# S7CAS-PLEIADES-CARTE-MERE_P20_DAC-ADC-De.net
KiCad netlist of a schematic drawn in Altium Designer
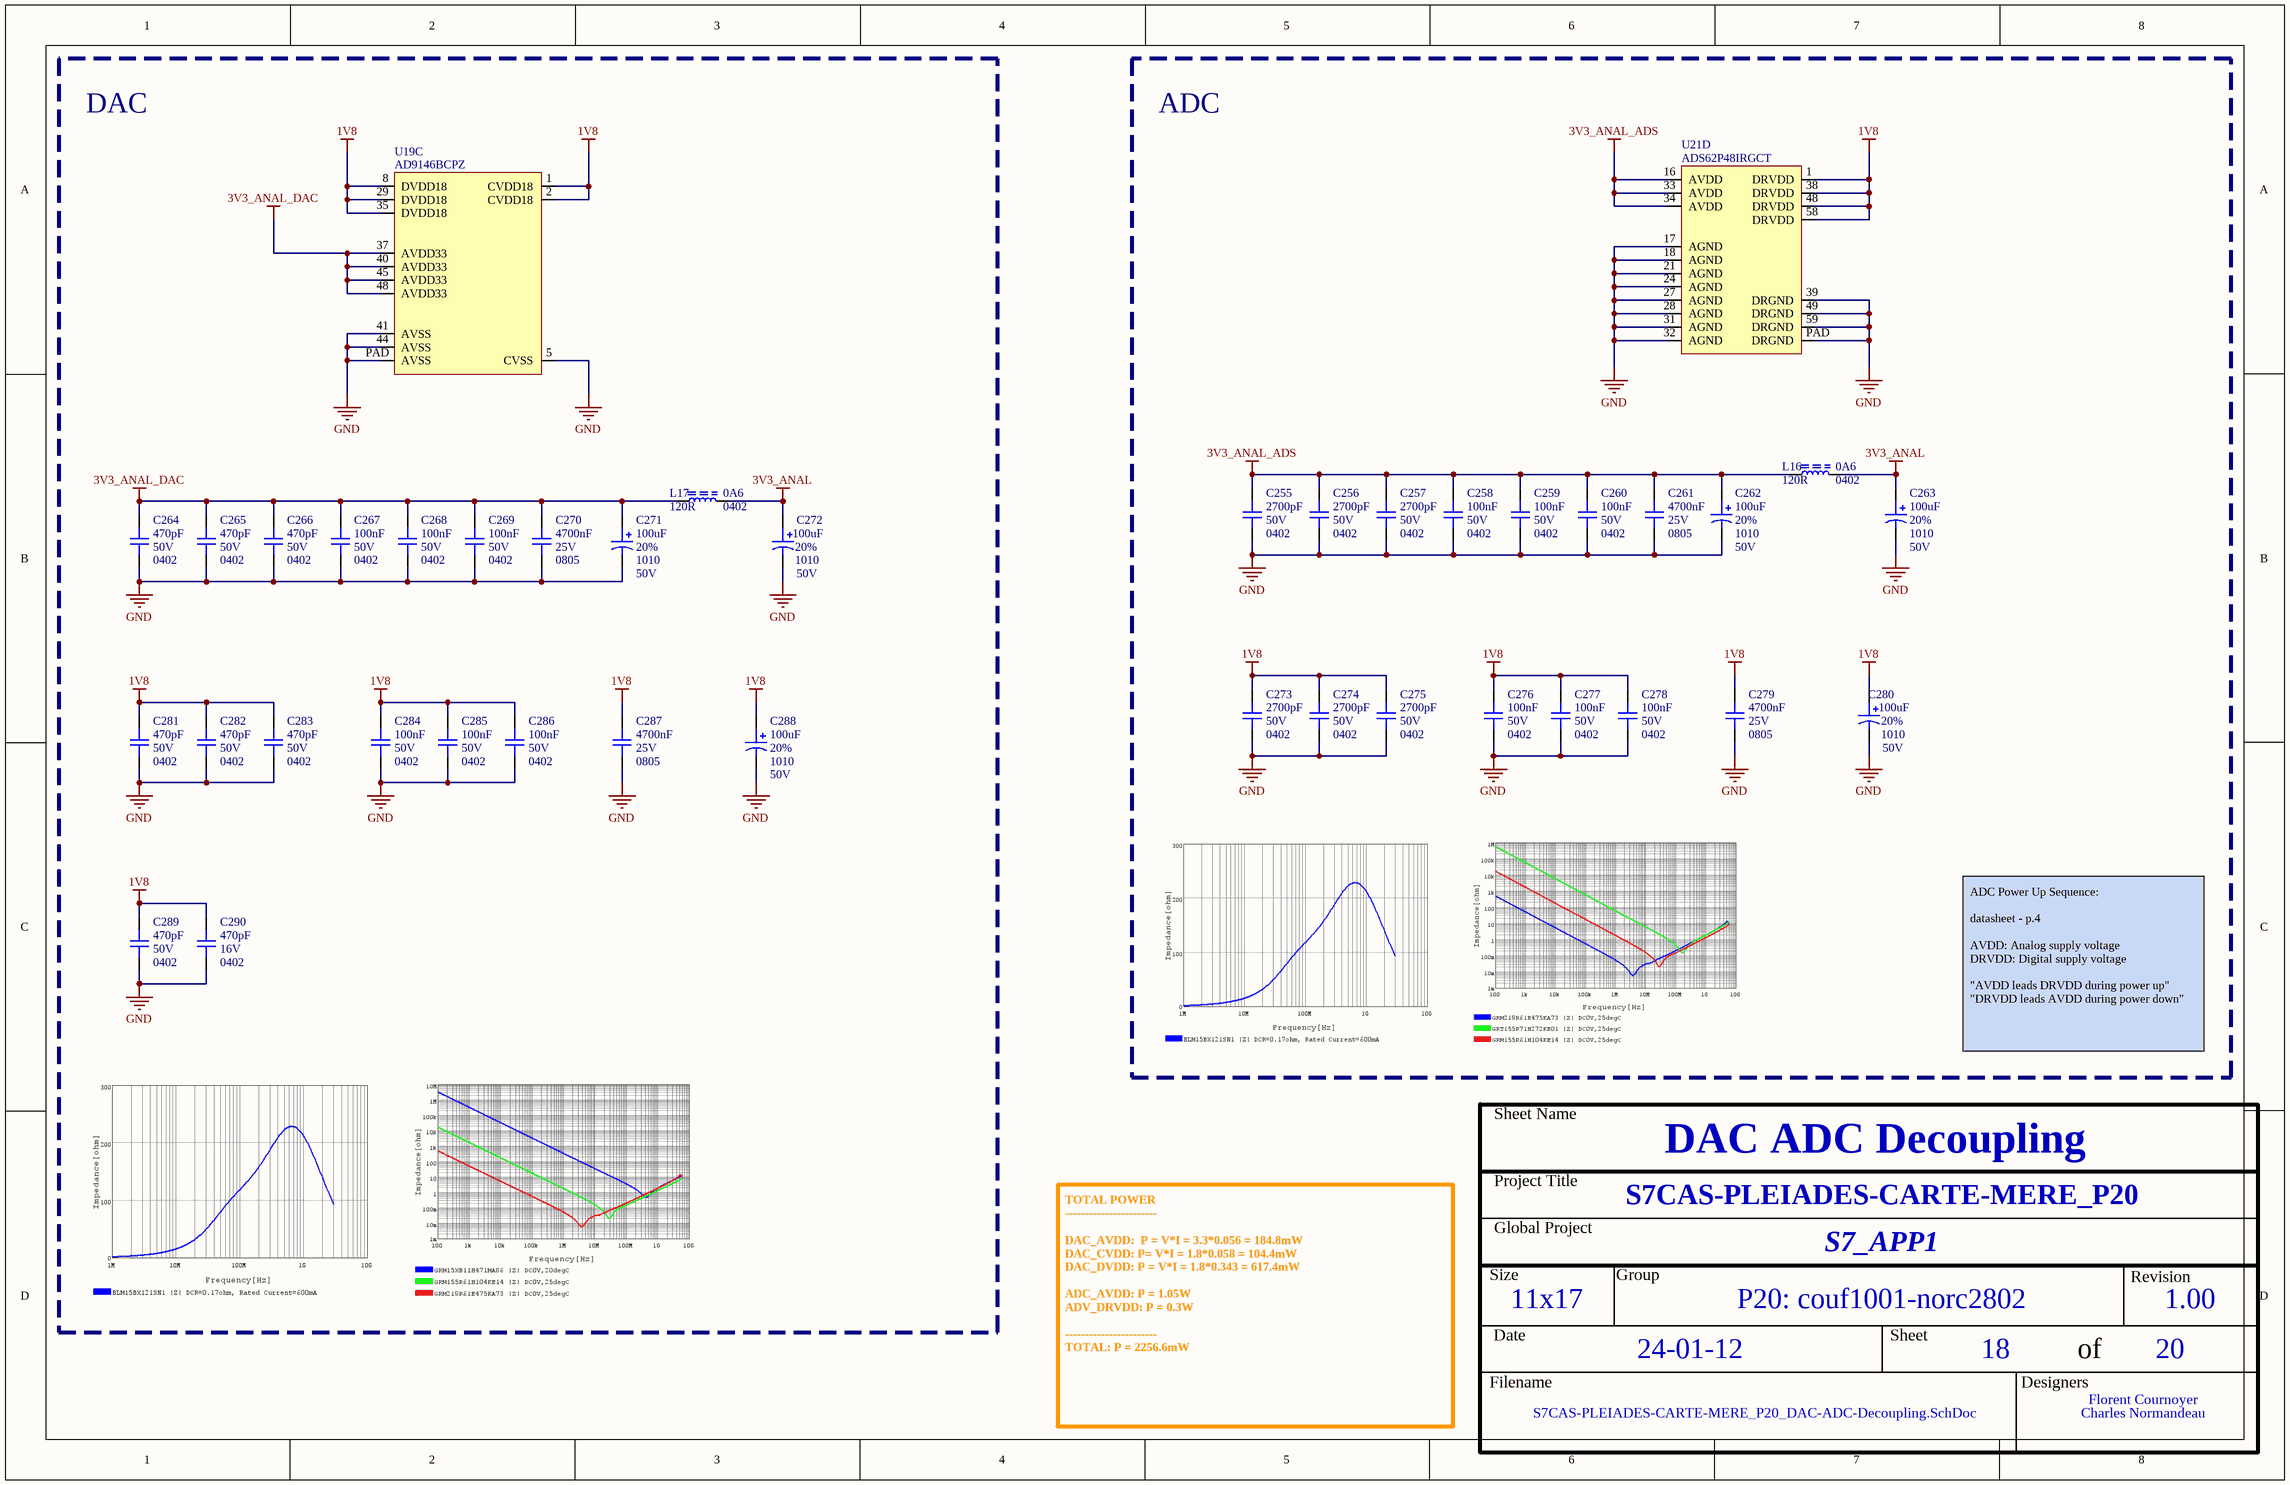
[diagram p0: S7CAS-PLEIADES-CARTE-MERE_P20_DAC-ADC-Decoupling.SchDoc]

(export (version "E")
  (design (tool "Eeschema 10.0.6"))
  (components
    (comp (ref "C255")
      (value "2700pF")
      (footprint "CAP_0402")
      (description "CAP - 0402")
      (fields
        (field (name "MFG PART NUMBER") "GRT155R71H272KE01")
        (field (name "VOLTAGE") "50V")
        (field (name "PACKAGE") "0402")
        (field (name "CREATEDBY") "Jonathan Bouchard")
      )
      (libsource (lib "S7CAS_LIB2023") (part "CAP - 0402"))
    )
    (comp (ref "C256")
      (value "2700pF")
      (footprint "CAP_0402")
      (description "CAP - 0402")
      (fields
        (field (name "MFG PART NUMBER") "GRT155R71H272KE01")
        (field (name "VOLTAGE") "50V")
        (field (name "PACKAGE") "0402")
        (field (name "CREATEDBY") "Jonathan Bouchard")
      )
      (libsource (lib "S7CAS_LIB2023") (part "CAP - 0402"))
    )
    (comp (ref "C257")
      (value "2700pF")
      (footprint "CAP_0402")
      (description "CAP - 0402")
      (fields
        (field (name "MFG PART NUMBER") "GRT155R71H272KE01")
        (field (name "VOLTAGE") "50V")
        (field (name "PACKAGE") "0402")
        (field (name "CREATEDBY") "Jonathan Bouchard")
      )
      (libsource (lib "S7CAS_LIB2023") (part "CAP - 0402"))
    )
    (comp (ref "C258")
      (value "100nF")
      (footprint "CAP_0402")
      (description "CAP - 0402")
      (fields
        (field (name "MFG PART NUMBER") "GRM155R61H104KE14")
        (field (name "VOLTAGE") "50V")
        (field (name "PACKAGE") "0402")
        (field (name "CREATEDBY") "Jonathan Bouchard")
      )
      (libsource (lib "S7CAS_LIB2023") (part "CAP - 0402"))
    )
    (comp (ref "C259")
      (value "100nF")
      (footprint "CAP_0402")
      (description "CAP - 0402")
      (fields
        (field (name "MFG PART NUMBER") "GRM155R61H104KE14")
        (field (name "VOLTAGE") "50V")
        (field (name "PACKAGE") "0402")
        (field (name "CREATEDBY") "Jonathan Bouchard")
      )
      (libsource (lib "S7CAS_LIB2023") (part "CAP - 0402"))
    )
    (comp (ref "C260")
      (value "100nF")
      (footprint "CAP_0402")
      (description "CAP - 0402")
      (fields
        (field (name "MFG PART NUMBER") "GRM155R61H104KE14")
        (field (name "VOLTAGE") "50V")
        (field (name "PACKAGE") "0402")
        (field (name "CREATEDBY") "Jonathan Bouchard")
      )
      (libsource (lib "S7CAS_LIB2023") (part "CAP - 0402"))
    )
    (comp (ref "C261")
      (value "4700nF")
      (footprint "CAP_0805")
      (description "CAP - 0805")
      (fields
        (field (name "MFG PART NUMBER") "GRM219R61E475KA73")
        (field (name "VOLTAGE") "25V")
        (field (name "PACKAGE") "0805")
        (field (name "CREATEDBY") "Jonathan Bouchard")
      )
      (libsource (lib "S7CAS_LIB2023") (part "CAP - 0805"))
    )
    (comp (ref "C262")
      (value "100uF")
      (footprint "CAP_ALU_1010_vishay")
      (description "CAP - ALU 100uF 20% 50V - 1010")
      (fields
        (field (name "MFG") "Vishay Dale")
        (field (name "MFG PART NUMBER") "MAL215099101E3")
        (field (name "VOLTAGE") "50V")
        (field (name "PACKAGE") "1010")
        (field (name "PRECISION") "20%")
        (field (name "CREATEDBY") "Jonathan Bouchard")
      )
      (libsource (lib "S7CAS_LIB2023") (part "CAP_ALU_MAL215099101E3"))
    )
    (comp (ref "C263")
      (value "100uF")
      (footprint "CAP_ALU_1010_vishay")
      (description "CAP - ALU 100uF 20% 50V - 1010")
      (fields
        (field (name "MFG") "Vishay Dale")
        (field (name "MFG PART NUMBER") "MAL215099101E3")
        (field (name "VOLTAGE") "50V")
        (field (name "PACKAGE") "1010")
        (field (name "PRECISION") "20%")
        (field (name "CREATEDBY") "Jonathan Bouchard")
      )
      (libsource (lib "S7CAS_LIB2023") (part "CAP_ALU_MAL215099101E3"))
    )
    (comp (ref "C264")
      (value "470pF")
      (footprint "CAP_0402")
      (description "CAP - 0402")
      (fields
        (field (name "MFG PART NUMBER") "GRM1555C1H471GA01")
        (field (name "VOLTAGE") "50V")
        (field (name "PACKAGE") "0402")
        (field (name "CREATEDBY") "Jonathan Bouchard")
      )
      (libsource (lib "S7CAS_LIB2023") (part "CAP - 0402"))
    )
    (comp (ref "C265")
      (value "470pF")
      (footprint "CAP_0402")
      (description "CAP - 0402")
      (fields
        (field (name "MFG PART NUMBER") "GRM1555C1H471GA01")
        (field (name "VOLTAGE") "50V")
        (field (name "PACKAGE") "0402")
        (field (name "CREATEDBY") "Jonathan Bouchard")
      )
      (libsource (lib "S7CAS_LIB2023") (part "CAP - 0402"))
    )
    (comp (ref "C266")
      (value "470pF")
      (footprint "CAP_0402")
      (description "CAP - 0402")
      (fields
        (field (name "MFG PART NUMBER") "GRM1555C1H471GA01")
        (field (name "VOLTAGE") "50V")
        (field (name "PACKAGE") "0402")
        (field (name "CREATEDBY") "Jonathan Bouchard")
      )
      (libsource (lib "S7CAS_LIB2023") (part "CAP - 0402"))
    )
    (comp (ref "C267")
      (value "100nF")
      (footprint "CAP_0402")
      (description "CAP - 0402")
      (fields
        (field (name "MFG PART NUMBER") "GRM155R61H104KE14")
        (field (name "VOLTAGE") "50V")
        (field (name "PACKAGE") "0402")
        (field (name "CREATEDBY") "Jonathan Bouchard")
      )
      (libsource (lib "S7CAS_LIB2023") (part "CAP - 0402"))
    )
    (comp (ref "C268")
      (value "100nF")
      (footprint "CAP_0402")
      (description "CAP - 0402")
      (fields
        (field (name "MFG PART NUMBER") "GRM155R61H104KE14")
        (field (name "VOLTAGE") "50V")
        (field (name "PACKAGE") "0402")
        (field (name "CREATEDBY") "Jonathan Bouchard")
      )
      (libsource (lib "S7CAS_LIB2023") (part "CAP - 0402"))
    )
    (comp (ref "C269")
      (value "100nF")
      (footprint "CAP_0402")
      (description "CAP - 0402")
      (fields
        (field (name "MFG PART NUMBER") "GRM155R61H104KE14")
        (field (name "VOLTAGE") "50V")
        (field (name "PACKAGE") "0402")
        (field (name "CREATEDBY") "Jonathan Bouchard")
      )
      (libsource (lib "S7CAS_LIB2023") (part "CAP - 0402"))
    )
    (comp (ref "C270")
      (value "4700nF")
      (footprint "CAP_0805")
      (description "CAP - 0805")
      (fields
        (field (name "MFG PART NUMBER") "GRM219R61E475KA73")
        (field (name "VOLTAGE") "25V")
        (field (name "PACKAGE") "0805")
        (field (name "CREATEDBY") "Jonathan Bouchard")
      )
      (libsource (lib "S7CAS_LIB2023") (part "CAP - 0805"))
    )
    (comp (ref "C271")
      (value "100uF")
      (footprint "CAP_ALU_1010_vishay")
      (description "CAP - ALU 100uF 20% 50V - 1010")
      (fields
        (field (name "MFG") "Vishay Dale")
        (field (name "MFG PART NUMBER") "MAL215099101E3")
        (field (name "VOLTAGE") "50V")
        (field (name "PACKAGE") "1010")
        (field (name "PRECISION") "20%")
        (field (name "CREATEDBY") "Jonathan Bouchard")
      )
      (libsource (lib "S7CAS_LIB2023") (part "CAP_ALU_MAL215099101E3"))
    )
    (comp (ref "C272")
      (value "100uF")
      (footprint "CAP_ALU_1010_vishay")
      (description "CAP - ALU 100uF 20% 50V - 1010")
      (fields
        (field (name "MFG") "Vishay Dale")
        (field (name "MFG PART NUMBER") "MAL215099101E3")
        (field (name "VOLTAGE") "50V")
        (field (name "PACKAGE") "1010")
        (field (name "PRECISION") "20%")
        (field (name "CREATEDBY") "Jonathan Bouchard")
      )
      (libsource (lib "S7CAS_LIB2023") (part "CAP_ALU_MAL215099101E3"))
    )
    (comp (ref "C273")
      (value "2700pF")
      (footprint "CAP_0402")
      (description "CAP - 0402")
      (fields
        (field (name "MFG PART NUMBER") "GRT155R71H272KE01")
        (field (name "VOLTAGE") "50V")
        (field (name "PACKAGE") "0402")
        (field (name "CREATEDBY") "Jonathan Bouchard")
      )
      (libsource (lib "S7CAS_LIB2023") (part "CAP - 0402"))
    )
    (comp (ref "C274")
      (value "2700pF")
      (footprint "CAP_0402")
      (description "CAP - 0402")
      (fields
        (field (name "MFG PART NUMBER") "GRT155R71H272KE01")
        (field (name "VOLTAGE") "50V")
        (field (name "PACKAGE") "0402")
        (field (name "CREATEDBY") "Jonathan Bouchard")
      )
      (libsource (lib "S7CAS_LIB2023") (part "CAP - 0402"))
    )
    (comp (ref "C275")
      (value "2700pF")
      (footprint "CAP_0402")
      (description "CAP - 0402")
      (fields
        (field (name "MFG PART NUMBER") "GRT155R71H272KE01")
        (field (name "VOLTAGE") "50V")
        (field (name "PACKAGE") "0402")
        (field (name "CREATEDBY") "Jonathan Bouchard")
      )
      (libsource (lib "S7CAS_LIB2023") (part "CAP - 0402"))
    )
    (comp (ref "C276")
      (value "100nF")
      (footprint "CAP_0402")
      (description "CAP - 0402")
      (fields
        (field (name "MFG PART NUMBER") "GRM155R61H104KE14")
        (field (name "VOLTAGE") "50V")
        (field (name "PACKAGE") "0402")
        (field (name "CREATEDBY") "Jonathan Bouchard")
      )
      (libsource (lib "S7CAS_LIB2023") (part "CAP - 0402"))
    )
    (comp (ref "C277")
      (value "100nF")
      (footprint "CAP_0402")
      (description "CAP - 0402")
      (fields
        (field (name "MFG PART NUMBER") "GRM155R61H104KE14")
        (field (name "VOLTAGE") "50V")
        (field (name "PACKAGE") "0402")
        (field (name "CREATEDBY") "Jonathan Bouchard")
      )
      (libsource (lib "S7CAS_LIB2023") (part "CAP - 0402"))
    )
    (comp (ref "C278")
      (value "100nF")
      (footprint "CAP_0402")
      (description "CAP - 0402")
      (fields
        (field (name "MFG PART NUMBER") "GRM155R61H104KE14")
        (field (name "VOLTAGE") "50V")
        (field (name "PACKAGE") "0402")
        (field (name "CREATEDBY") "Jonathan Bouchard")
      )
      (libsource (lib "S7CAS_LIB2023") (part "CAP - 0402"))
    )
    (comp (ref "C279")
      (value "4700nF")
      (footprint "CAP_0805")
      (description "CAP - 0805")
      (fields
        (field (name "MFG PART NUMBER") "GRM219R61E475KA73")
        (field (name "VOLTAGE") "25V")
        (field (name "PACKAGE") "0805")
        (field (name "CREATEDBY") "Jonathan Bouchard")
      )
      (libsource (lib "S7CAS_LIB2023") (part "CAP - 0805"))
    )
    (comp (ref "C280")
      (value "100uF")
      (footprint "CAP_ALU_1010_vishay")
      (description "CAP - ALU 100uF 20% 50V - 1010")
      (fields
        (field (name "MFG") "Vishay Dale")
        (field (name "MFG PART NUMBER") "MAL215099101E3")
        (field (name "VOLTAGE") "50V")
        (field (name "PACKAGE") "1010")
        (field (name "PRECISION") "20%")
        (field (name "CREATEDBY") "Jonathan Bouchard")
      )
      (libsource (lib "S7CAS_LIB2023") (part "CAP_ALU_MAL215099101E3"))
    )
    (comp (ref "C281")
      (value "470pF")
      (footprint "CAP_0402")
      (description "CAP - 0402")
      (fields
        (field (name "MFG PART NUMBER") "GRM1555C1H471GA01")
        (field (name "VOLTAGE") "50V")
        (field (name "PACKAGE") "0402")
        (field (name "CREATEDBY") "Jonathan Bouchard")
      )
      (libsource (lib "S7CAS_LIB2023") (part "CAP - 0402"))
    )
    (comp (ref "C282")
      (value "470pF")
      (footprint "CAP_0402")
      (description "CAP - 0402")
      (fields
        (field (name "MFG PART NUMBER") "GRM1555C1H471GA01")
        (field (name "VOLTAGE") "50V")
        (field (name "PACKAGE") "0402")
        (field (name "CREATEDBY") "Jonathan Bouchard")
      )
      (libsource (lib "S7CAS_LIB2023") (part "CAP - 0402"))
    )
    (comp (ref "C283")
      (value "470pF")
      (footprint "CAP_0402")
      (description "CAP - 0402")
      (fields
        (field (name "MFG PART NUMBER") "GRM1555C1H471GA01")
        (field (name "VOLTAGE") "50V")
        (field (name "PACKAGE") "0402")
        (field (name "CREATEDBY") "Jonathan Bouchard")
      )
      (libsource (lib "S7CAS_LIB2023") (part "CAP - 0402"))
    )
    (comp (ref "C284")
      (value "100nF")
      (footprint "CAP_0402")
      (description "CAP - 0402")
      (fields
        (field (name "MFG PART NUMBER") "GRM155R61H104KE14")
        (field (name "VOLTAGE") "50V")
        (field (name "PACKAGE") "0402")
        (field (name "CREATEDBY") "Jonathan Bouchard")
      )
      (libsource (lib "S7CAS_LIB2023") (part "CAP - 0402"))
    )
    (comp (ref "C285")
      (value "100nF")
      (footprint "CAP_0402")
      (description "CAP - 0402")
      (fields
        (field (name "MFG PART NUMBER") "GRM155R61H104KE14")
        (field (name "VOLTAGE") "50V")
        (field (name "PACKAGE") "0402")
        (field (name "CREATEDBY") "Jonathan Bouchard")
      )
      (libsource (lib "S7CAS_LIB2023") (part "CAP - 0402"))
    )
    (comp (ref "C286")
      (value "100nF")
      (footprint "CAP_0402")
      (description "CAP - 0402")
      (fields
        (field (name "MFG PART NUMBER") "GRM155R61H104KE14")
        (field (name "VOLTAGE") "50V")
        (field (name "PACKAGE") "0402")
        (field (name "CREATEDBY") "Jonathan Bouchard")
      )
      (libsource (lib "S7CAS_LIB2023") (part "CAP - 0402"))
    )
    (comp (ref "C287")
      (value "4700nF")
      (footprint "CAP_0805")
      (description "CAP - 0805")
      (fields
        (field (name "MFG PART NUMBER") "GRM219R61E475KA73")
        (field (name "VOLTAGE") "25V")
        (field (name "PACKAGE") "0805")
        (field (name "CREATEDBY") "Jonathan Bouchard")
      )
      (libsource (lib "S7CAS_LIB2023") (part "CAP - 0805"))
    )
    (comp (ref "C288")
      (value "100uF")
      (footprint "CAP_ALU_1010_vishay")
      (description "CAP - ALU 100uF 20% 50V - 1010")
      (fields
        (field (name "MFG") "Vishay Dale")
        (field (name "MFG PART NUMBER") "MAL215099101E3")
        (field (name "VOLTAGE") "50V")
        (field (name "PACKAGE") "1010")
        (field (name "PRECISION") "20%")
        (field (name "CREATEDBY") "Jonathan Bouchard")
      )
      (libsource (lib "S7CAS_LIB2023") (part "CAP_ALU_MAL215099101E3"))
    )
    (comp (ref "C289")
      (value "470pF")
      (footprint "CAP_0402")
      (description "CAP - 0402")
      (fields
        (field (name "MFG PART NUMBER") "GRM1555C1H471GA01")
        (field (name "VOLTAGE") "50V")
        (field (name "PACKAGE") "0402")
        (field (name "CREATEDBY") "Jonathan Bouchard")
      )
      (libsource (lib "S7CAS_LIB2023") (part "CAP - 0402"))
    )
    (comp (ref "C290")
      (value "470pF")
      (footprint "CAP_0402")
      (description "CAP - 0402")
      (fields
        (field (name "MFG PART NUMBER") "GRM15XB11H471MA86")
        (field (name "VOLTAGE") "16V")
        (field (name "PACKAGE") "0402")
        (field (name "CREATEDBY") "Jonathan Bouchard")
      )
      (libsource (lib "S7CAS_LIB2023") (part "CAP - 0402"))
    )
    (comp (ref "L16")
      (value "120R")
      (footprint "FER_0402")
      (description "FER - 0402")
      (fields
        (field (name "MFG PART NUMBER") "BLM15BX121SN1")
        (field (name "CURRENT") "0A6")
        (field (name "PACKAGE") "0402")
        (field (name "CREATEDBY") "Jonathan Bouchard")
      )
      (libsource (lib "S7CAS_LIB2023") (part "FER - 0402"))
    )
    (comp (ref "L17")
      (value "120R")
      (footprint "FER_0402")
      (description "FER - 0402")
      (fields
        (field (name "MFG PART NUMBER") "BLM15BX121SN1")
        (field (name "CURRENT") "0A6")
        (field (name "PACKAGE") "0402")
        (field (name "CREATEDBY") "Jonathan Bouchard")
      )
      (libsource (lib "S7CAS_LIB2023") (part "FER - 0402"))
    )
    (comp (ref "U19")
      (value "AD9146BCPZ")
      (footprint "DAC_AD9146BCPZ")
      (description "DAC - 16BIT SRL HIGH SPEED - QFN-48")
      (fields
        (field (name "VOLTAGE") "3.13 V ~ 3.47 V / 1.71 V ~ 1.89 V")
        (field (name "MFG") "Analog Devices Inc.")
        (field (name "CREATEDBY") "Jonathan Bouchard")
      )
      (libsource (lib "S7CAS_LIB2023") (part "DAC_AD9146BCPZ"))
    )
    (comp (ref "U21")
      (value "ADS62P48IRGCT")
      (footprint "ADC_ADS62P48IRGCT")
      (description "ADC - 14 BIT 210MSPS SUAL - VQFN-64")
      (fields
        (field (name "VOLTAGE") "3.15 V ~ 3.6 V / 1.7 V ~ 1.9 V")
        (field (name "MFG") "Texas Instruments")
        (field (name "CREATEDBY") "Jonathan Bouchard")
      )
      (libsource (lib "S7CAS_LIB2023") (part "ADC_ADS62P48IRGCT"))
    )
  )
  (nets
    (net (code "1") (name "1V8") (class "Default")
      (node (ref "C273") (pin "2") (pinfunction "2_2") (pintype "passive"))
      (node (ref "C274") (pin "2") (pinfunction "2_2") (pintype "passive"))
      (node (ref "C275") (pin "2") (pinfunction "2_2") (pintype "passive"))
      (node (ref "C276") (pin "2") (pinfunction "2_2") (pintype "passive"))
      (node (ref "C277") (pin "2") (pinfunction "2_2") (pintype "passive"))
      (node (ref "C278") (pin "2") (pinfunction "2_2") (pintype "passive"))
      (node (ref "C279") (pin "2") (pinfunction "2_2") (pintype "passive"))
      (node (ref "C280") (pin "1") (pinfunction "1_1") (pintype "passive"))
      (node (ref "C281") (pin "2") (pinfunction "2_2") (pintype "passive"))
      (node (ref "C282") (pin "2") (pinfunction "2_2") (pintype "passive"))
      (node (ref "C283") (pin "2") (pinfunction "2_2") (pintype "passive"))
      (node (ref "C284") (pin "2") (pinfunction "2_2") (pintype "passive"))
      (node (ref "C285") (pin "2") (pinfunction "2_2") (pintype "passive"))
      (node (ref "C286") (pin "2") (pinfunction "2_2") (pintype "passive"))
      (node (ref "C287") (pin "2") (pinfunction "2_2") (pintype "passive"))
      (node (ref "C288") (pin "1") (pinfunction "1_1") (pintype "passive"))
      (node (ref "C289") (pin "2") (pinfunction "2_2") (pintype "passive"))
      (node (ref "C290") (pin "2") (pinfunction "2_2") (pintype "passive"))
      (node (ref "U19") (pin "1") (pinfunction "CVDD18_1") (pintype "passive"))
      (node (ref "U19") (pin "2") (pinfunction "CVDD18_2") (pintype "passive"))
      (node (ref "U19") (pin "29") (pinfunction "DVDD18_29") (pintype "passive"))
      (node (ref "U19") (pin "35") (pinfunction "DVDD18_35") (pintype "passive"))
      (node (ref "U19") (pin "8") (pinfunction "DVDD18_8") (pintype "passive"))
      (node (ref "U21") (pin "1") (pinfunction "DRVDD_1") (pintype "passive"))
      (node (ref "U21") (pin "38") (pinfunction "DRVDD_38") (pintype "passive"))
      (node (ref "U21") (pin "48") (pinfunction "DRVDD_48") (pintype "passive"))
      (node (ref "U21") (pin "58") (pinfunction "DRVDD_58") (pintype "passive"))
    )
    (net (code "2") (name "3V3_ANAL") (class "Default")
      (node (ref "C263") (pin "1") (pinfunction "1_1") (pintype "passive"))
      (node (ref "C272") (pin "1") (pinfunction "1_1") (pintype "passive"))
      (node (ref "L16") (pin "1") (pinfunction "1_1") (pintype "passive"))
      (node (ref "L17") (pin "1") (pinfunction "1_1") (pintype "passive"))
    )
    (net (code "3") (name "3V3_ANAL_ADS") (class "Default")
      (node (ref "C255") (pin "2") (pinfunction "2_2") (pintype "passive"))
      (node (ref "C256") (pin "2") (pinfunction "2_2") (pintype "passive"))
      (node (ref "C257") (pin "2") (pinfunction "2_2") (pintype "passive"))
      (node (ref "C258") (pin "2") (pinfunction "2_2") (pintype "passive"))
      (node (ref "C259") (pin "2") (pinfunction "2_2") (pintype "passive"))
      (node (ref "C260") (pin "2") (pinfunction "2_2") (pintype "passive"))
      (node (ref "C261") (pin "2") (pinfunction "2_2") (pintype "passive"))
      (node (ref "C262") (pin "1") (pinfunction "1_1") (pintype "passive"))
      (node (ref "L16") (pin "2") (pinfunction "2_2") (pintype "passive"))
      (node (ref "U21") (pin "16") (pinfunction "AVDD_16") (pintype "passive"))
      (node (ref "U21") (pin "33") (pinfunction "AVDD_33") (pintype "passive"))
      (node (ref "U21") (pin "34") (pinfunction "AVDD_34") (pintype "passive"))
    )
    (net (code "4") (name "3V3_ANAL_DAC") (class "Default")
      (node (ref "C264") (pin "2") (pinfunction "2_2") (pintype "passive"))
      (node (ref "C265") (pin "2") (pinfunction "2_2") (pintype "passive"))
      (node (ref "C266") (pin "2") (pinfunction "2_2") (pintype "passive"))
      (node (ref "C267") (pin "2") (pinfunction "2_2") (pintype "passive"))
      (node (ref "C268") (pin "2") (pinfunction "2_2") (pintype "passive"))
      (node (ref "C269") (pin "2") (pinfunction "2_2") (pintype "passive"))
      (node (ref "C270") (pin "2") (pinfunction "2_2") (pintype "passive"))
      (node (ref "C271") (pin "1") (pinfunction "1_1") (pintype "passive"))
      (node (ref "L17") (pin "2") (pinfunction "2_2") (pintype "passive"))
      (node (ref "U19") (pin "37") (pinfunction "AVDD33_37") (pintype "passive"))
      (node (ref "U19") (pin "40") (pinfunction "AVDD33_40") (pintype "passive"))
      (node (ref "U19") (pin "45") (pinfunction "AVDD33_45") (pintype "passive"))
      (node (ref "U19") (pin "48") (pinfunction "AVDD33_48") (pintype "passive"))
    )
    (net (code "5") (name "GND") (class "Default")
      (node (ref "C255") (pin "1") (pinfunction "1_1") (pintype "passive"))
      (node (ref "C256") (pin "1") (pinfunction "1_1") (pintype "passive"))
      (node (ref "C257") (pin "1") (pinfunction "1_1") (pintype "passive"))
      (node (ref "C258") (pin "1") (pinfunction "1_1") (pintype "passive"))
      (node (ref "C259") (pin "1") (pinfunction "1_1") (pintype "passive"))
      (node (ref "C260") (pin "1") (pinfunction "1_1") (pintype "passive"))
      (node (ref "C261") (pin "1") (pinfunction "1_1") (pintype "passive"))
      (node (ref "C262") (pin "2") (pinfunction "2_2") (pintype "passive"))
      (node (ref "C263") (pin "2") (pinfunction "2_2") (pintype "passive"))
      (node (ref "C264") (pin "1") (pinfunction "1_1") (pintype "passive"))
      (node (ref "C265") (pin "1") (pinfunction "1_1") (pintype "passive"))
      (node (ref "C266") (pin "1") (pinfunction "1_1") (pintype "passive"))
      (node (ref "C267") (pin "1") (pinfunction "1_1") (pintype "passive"))
      (node (ref "C268") (pin "1") (pinfunction "1_1") (pintype "passive"))
      (node (ref "C269") (pin "1") (pinfunction "1_1") (pintype "passive"))
      (node (ref "C270") (pin "1") (pinfunction "1_1") (pintype "passive"))
      (node (ref "C271") (pin "2") (pinfunction "2_2") (pintype "passive"))
      (node (ref "C272") (pin "2") (pinfunction "2_2") (pintype "passive"))
      (node (ref "C273") (pin "1") (pinfunction "1_1") (pintype "passive"))
      (node (ref "C274") (pin "1") (pinfunction "1_1") (pintype "passive"))
      (node (ref "C275") (pin "1") (pinfunction "1_1") (pintype "passive"))
      (node (ref "C276") (pin "1") (pinfunction "1_1") (pintype "passive"))
      (node (ref "C277") (pin "1") (pinfunction "1_1") (pintype "passive"))
      (node (ref "C278") (pin "1") (pinfunction "1_1") (pintype "passive"))
      (node (ref "C279") (pin "1") (pinfunction "1_1") (pintype "passive"))
      (node (ref "C280") (pin "2") (pinfunction "2_2") (pintype "passive"))
      (node (ref "C281") (pin "1") (pinfunction "1_1") (pintype "passive"))
      (node (ref "C282") (pin "1") (pinfunction "1_1") (pintype "passive"))
      (node (ref "C283") (pin "1") (pinfunction "1_1") (pintype "passive"))
      (node (ref "C284") (pin "1") (pinfunction "1_1") (pintype "passive"))
      (node (ref "C285") (pin "1") (pinfunction "1_1") (pintype "passive"))
      (node (ref "C286") (pin "1") (pinfunction "1_1") (pintype "passive"))
      (node (ref "C287") (pin "1") (pinfunction "1_1") (pintype "passive"))
      (node (ref "C288") (pin "2") (pinfunction "2_2") (pintype "passive"))
      (node (ref "C289") (pin "1") (pinfunction "1_1") (pintype "passive"))
      (node (ref "C290") (pin "1") (pinfunction "1_1") (pintype "passive"))
      (node (ref "U19") (pin "41") (pinfunction "AVSS_41") (pintype "passive"))
      (node (ref "U19") (pin "44") (pinfunction "AVSS_44") (pintype "passive"))
      (node (ref "U19") (pin "5") (pinfunction "CVSS_5") (pintype "passive"))
      (node (ref "U19") (pin "PAD") (pinfunction "AVSS_PAD") (pintype "passive"))
      (node (ref "U21") (pin "17") (pinfunction "AGND_17") (pintype "passive"))
      (node (ref "U21") (pin "18") (pinfunction "AGND_18") (pintype "passive"))
      (node (ref "U21") (pin "21") (pinfunction "AGND_21") (pintype "passive"))
      (node (ref "U21") (pin "24") (pinfunction "AGND_24") (pintype "passive"))
      (node (ref "U21") (pin "27") (pinfunction "AGND_27") (pintype "passive"))
      (node (ref "U21") (pin "28") (pinfunction "AGND_28") (pintype "passive"))
      (node (ref "U21") (pin "31") (pinfunction "AGND_31") (pintype "passive"))
      (node (ref "U21") (pin "32") (pinfunction "AGND_32") (pintype "passive"))
      (node (ref "U21") (pin "39") (pinfunction "DRGND_39") (pintype "passive"))
      (node (ref "U21") (pin "49") (pinfunction "DRGND_49") (pintype "passive"))
      (node (ref "U21") (pin "59") (pinfunction "DRGND_59") (pintype "passive"))
      (node (ref "U21") (pin "PAD") (pinfunction "DRGND_PAD") (pintype "passive"))
    )
  )
)
